# PowerPinsBlockingLED.net
KiCad netlist of a schematic drawn in Altium Designer
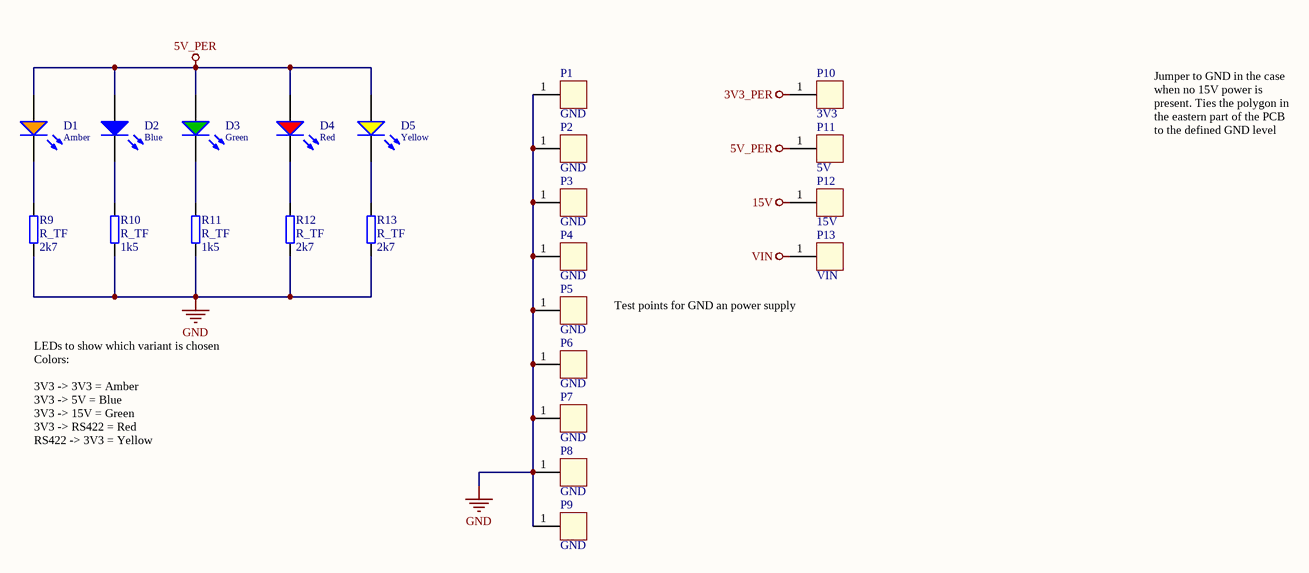
[diagram p0: PowerPinsBlockingLED.SchDoc]

(export (version "E")
  (design (tool "Eeschema 10.0.6"))
  (components
    (comp (ref "D1")
      (value "LED_Amber")
      (footprint "WL-SMCW_0603")
      (description "WL-SMCW SMD Mono-color Chip LED Waterclear, size 0603, Red, 2 V, 140°")
      (fields
        (field (name "EMITTING COLOR") "Amber")
        (field (name "MPN") "150060AS75000")
        (field (name "MF") "Wuerth Elektronik")
        (field (name "CREATED") "2020-01-07_Thilo_Wendt")
      )
      (libsource (lib "optoelectronics") (part "LED_Amber"))
    )
    (comp (ref "D2")
      (value "LED_Blue")
      (footprint "WL-SMCW_0603")
      (description "WL-SMCW SMD Mono-color Chip LED Waterclear, size 0603, Blue, 3.2 V, 140°")
      (fields
        (field (name "MPN") "150060BS75000")
        (field (name "MF") "Wuerth Elektronik")
        (field (name "EMITTING COLOR") "Blue")
        (field (name "CREATED") "2018_09_06_AGeiger")
      )
      (libsource (lib "optoelectronics") (part "LED_Blue"))
    )
    (comp (ref "D3")
      (value "LED_Green")
      (footprint "WL-SMCW_0603")
      (description "WL-SMCW SMD Mono-color Chip LED Waterclear, size 0603, Green, 3.2 V, 140°")
      (fields
        (field (name "MPN") "150060GS75000")
        (field (name "MF") "Wuerth Elektronik")
        (field (name "EMITTING COLOR") "Green")
        (field (name "CREATED") "2018_09_06_AGeiger")
      )
      (libsource (lib "optoelectronics") (part "LED_Green"))
    )
    (comp (ref "D4")
      (value "LED_red")
      (footprint "WL-SMCW_0603")
      (description "WL-SMCW SMD Mono-color Chip LED Waterclear, size 0603, Red, 2 V, 140°")
      (fields
        (field (name "MPN") "150060RS75000")
        (field (name "MF") "Wuerth Elektronik")
        (field (name "EMITTING COLOR") "Red")
        (field (name "CREATED") "2018_09_06_AGeiger")
      )
      (libsource (lib "optoelectronics") (part "LED_Red"))
    )
    (comp (ref "D5")
      (value "LED_Yellow")
      (footprint "WL-SMCW_0603")
      (description "WL-SMCW SMD Mono-color Chip LED Waterclear, size 0603, Red, 2 V, 140°")
      (fields
        (field (name "EMITTING COLOR") "Yellow")
        (field (name "MPN") "150060YS75000")
        (field (name "MF") "Wuerth Elektronik")
        (field (name "CREATED") "2020-01-07_Thilo_Wendt")
      )
      (libsource (lib "optoelectronics") (part "LED_Yellow"))
    )
    (comp (ref "P1")
      (value "GND")
      (footprint "PinHeader1")
      (description "Pin Header with 1 terminal")
      (fields (field (name "CREATED") "2020-01-08_Thilo_Wendt"))
      (libsource (lib "connectors") (part "PinHeader1"))
    )
    (comp (ref "P2")
      (value "GND")
      (footprint "PinHeader1")
      (description "Pin Header with 1 terminal")
      (fields (field (name "CREATED") "2020-01-08_Thilo_Wendt"))
      (libsource (lib "connectors") (part "PinHeader1"))
    )
    (comp (ref "P3")
      (value "GND")
      (footprint "PinHeader1")
      (description "Pin Header with 1 terminal")
      (fields (field (name "CREATED") "2020-01-08_Thilo_Wendt"))
      (libsource (lib "connectors") (part "PinHeader1"))
    )
    (comp (ref "P4")
      (value "GND")
      (footprint "PinHeader1")
      (description "Pin Header with 1 terminal")
      (fields (field (name "CREATED") "2020-01-08_Thilo_Wendt"))
      (libsource (lib "connectors") (part "PinHeader1"))
    )
    (comp (ref "P5")
      (value "GND")
      (footprint "PinHeader1")
      (description "Pin Header with 1 terminal")
      (fields (field (name "CREATED") "2020-01-08_Thilo_Wendt"))
      (libsource (lib "connectors") (part "PinHeader1"))
    )
    (comp (ref "P6")
      (value "GND")
      (footprint "PinHeader1")
      (description "Pin Header with 1 terminal")
      (fields (field (name "CREATED") "2020-01-08_Thilo_Wendt"))
      (libsource (lib "connectors") (part "PinHeader1"))
    )
    (comp (ref "P7")
      (value "GND")
      (footprint "PinHeader1")
      (description "Pin Header with 1 terminal")
      (fields (field (name "CREATED") "2020-01-08_Thilo_Wendt"))
      (libsource (lib "connectors") (part "PinHeader1"))
    )
    (comp (ref "P8")
      (value "GND")
      (footprint "PinHeader1")
      (description "Pin Header with 1 terminal")
      (fields (field (name "CREATED") "2020-01-08_Thilo_Wendt"))
      (libsource (lib "connectors") (part "PinHeader1"))
    )
    (comp (ref "P9")
      (value "GND")
      (footprint "PinHeader1")
      (description "Pin Header with 1 terminal")
      (fields (field (name "CREATED") "2020-01-08_Thilo_Wendt"))
      (libsource (lib "connectors") (part "PinHeader1"))
    )
    (comp (ref "P10")
      (value "3V3")
      (footprint "PinHeader1")
      (description "Pin Header with 1 terminal")
      (fields (field (name "CREATED") "2020-01-08_Thilo_Wendt"))
      (libsource (lib "connectors") (part "PinHeader1"))
    )
    (comp (ref "P11")
      (value "5V")
      (footprint "PinHeader1")
      (description "Pin Header with 1 terminal")
      (fields (field (name "CREATED") "2020-01-08_Thilo_Wendt"))
      (libsource (lib "connectors") (part "PinHeader1"))
    )
    (comp (ref "P12")
      (value "15V")
      (footprint "PinHeader1")
      (description "Pin Header with 1 terminal")
      (fields (field (name "CREATED") "2020-01-08_Thilo_Wendt"))
      (libsource (lib "connectors") (part "PinHeader1"))
    )
    (comp (ref "P13")
      (value "VIN")
      (footprint "PinHeader1")
      (description "Pin Header with 1 terminal")
      (fields (field (name "CREATED") "2020-01-08_Thilo_Wendt"))
      (libsource (lib "connectors") (part "PinHeader1"))
    )
    (comp (ref "R9")
      (value "R_TF")
      (footprint "RESC1608X55X30NL15T15")
      (description "Standard thick film resistor")
      (fields
        (field (name "ALTIUM_VALUE") "2k7")
        (field (name "MF") "Panasonic")
        (field (name "MPN") "ERJU03F1501V")
        (field (name "CREATED") "2019-12-08_Thilo_Wendt")
      )
      (libsource (lib "standard_rlc") (part "R_0.1W_SMD"))
    )
    (comp (ref "R10")
      (value "R_TF")
      (footprint "RESC1608X55X30NL15T15")
      (description "Standard thick film resistor")
      (fields
        (field (name "ALTIUM_VALUE") "1k5")
        (field (name "MF") "Panasonic")
        (field (name "MPN") "ERJU03F2701V")
        (field (name "CREATED") "2019-12-08_Thilo_Wendt")
      )
      (libsource (lib "standard_rlc") (part "R_0.1W_SMD"))
    )
    (comp (ref "R11")
      (value "R_TF")
      (footprint "RESC1608X55X30NL15T15")
      (description "Standard thick film resistor")
      (fields
        (field (name "ALTIUM_VALUE") "1k5")
        (field (name "MF") "Panasonic")
        (field (name "MPN") "ERJU03F2701V")
        (field (name "CREATED") "2019-12-08_Thilo_Wendt")
      )
      (libsource (lib "standard_rlc") (part "R_0.1W_SMD"))
    )
    (comp (ref "R12")
      (value "R_TF")
      (footprint "RESC1608X55X30NL15T15")
      (description "Standard thick film resistor")
      (fields
        (field (name "ALTIUM_VALUE") "2k7")
        (field (name "MF") "Panasonic")
        (field (name "MPN") "ERJU03F1501V")
        (field (name "CREATED") "2019-12-08_Thilo_Wendt")
      )
      (libsource (lib "standard_rlc") (part "R_0.1W_SMD"))
    )
    (comp (ref "R13")
      (value "R_TF")
      (footprint "RESC1608X55X30NL15T15")
      (description "Standard thick film resistor")
      (fields
        (field (name "ALTIUM_VALUE") "2k7")
        (field (name "MF") "Panasonic")
        (field (name "MPN") "ERJU03F1501V")
        (field (name "CREATED") "2019-12-08_Thilo_Wendt")
      )
      (libsource (lib "standard_rlc") (part "R_0.1W_SMD"))
    )
  )
  (nets
    (net (code "1") (name "3V3_PER") (class "Default")
      (node (ref "P10") (pin "1") (pinfunction "1_1") (pintype "passive"))
    )
    (net (code "2") (name "5V_PER") (class "Default")
      (node (ref "D1") (pin "2") (pinfunction "A_2") (pintype "passive"))
      (node (ref "D2") (pin "2") (pinfunction "A_2") (pintype "passive"))
      (node (ref "D3") (pin "2") (pinfunction "A_2") (pintype "passive"))
      (node (ref "D4") (pin "2") (pinfunction "A_2") (pintype "passive"))
      (node (ref "D5") (pin "2") (pinfunction "A_2") (pintype "passive"))
      (node (ref "P11") (pin "1") (pinfunction "1_1") (pintype "passive"))
    )
    (net (code "3") (name "15V") (class "Default")
      (node (ref "P12") (pin "1") (pinfunction "1_1") (pintype "passive"))
    )
    (net (code "4") (name "GND") (class "Default")
      (node (ref "P1") (pin "1") (pinfunction "1_1") (pintype "passive"))
      (node (ref "P2") (pin "1") (pinfunction "1_1") (pintype "passive"))
      (node (ref "P3") (pin "1") (pinfunction "1_1") (pintype "passive"))
      (node (ref "P4") (pin "1") (pinfunction "1_1") (pintype "passive"))
      (node (ref "P5") (pin "1") (pinfunction "1_1") (pintype "passive"))
      (node (ref "P6") (pin "1") (pinfunction "1_1") (pintype "passive"))
      (node (ref "P7") (pin "1") (pinfunction "1_1") (pintype "passive"))
      (node (ref "P8") (pin "1") (pinfunction "1_1") (pintype "passive"))
      (node (ref "P9") (pin "1") (pinfunction "1_1") (pintype "passive"))
      (node (ref "R10") (pin "2") (pinfunction "2_2") (pintype "passive"))
      (node (ref "R11") (pin "2") (pinfunction "2_2") (pintype "passive"))
      (node (ref "R12") (pin "2") (pinfunction "2_2") (pintype "passive"))
      (node (ref "R13") (pin "2") (pinfunction "2_2") (pintype "passive"))
      (node (ref "R9") (pin "2") (pinfunction "2_2") (pintype "passive"))
    )
    (net (code "5") (name "Net-(D1-K)") (class "Default")
      (node (ref "D1") (pin "1") (pinfunction "K_1") (pintype "passive"))
      (node (ref "R9") (pin "1") (pinfunction "1_1") (pintype "passive"))
    )
    (net (code "6") (name "Net-(D2-K)") (class "Default")
      (node (ref "D2") (pin "1") (pinfunction "K_1") (pintype "passive"))
      (node (ref "R10") (pin "1") (pinfunction "1_1") (pintype "passive"))
    )
    (net (code "7") (name "Net-(D3-K)") (class "Default")
      (node (ref "D3") (pin "1") (pinfunction "K_1") (pintype "passive"))
      (node (ref "R11") (pin "1") (pinfunction "1_1") (pintype "passive"))
    )
    (net (code "8") (name "Net-(D4-K)") (class "Default")
      (node (ref "D4") (pin "1") (pinfunction "K_1") (pintype "passive"))
      (node (ref "R12") (pin "1") (pinfunction "1_1") (pintype "passive"))
    )
    (net (code "9") (name "Net-(D5-K)") (class "Default")
      (node (ref "D5") (pin "1") (pinfunction "K_1") (pintype "passive"))
      (node (ref "R13") (pin "1") (pinfunction "1_1") (pintype "passive"))
    )
    (net (code "10") (name "VIN") (class "Default")
      (node (ref "P13") (pin "1") (pinfunction "1_1") (pintype "passive"))
    )
  )
)
